# fortuna_v21_othermill.net
KiCad netlist of a schematic drawn in EAGLE
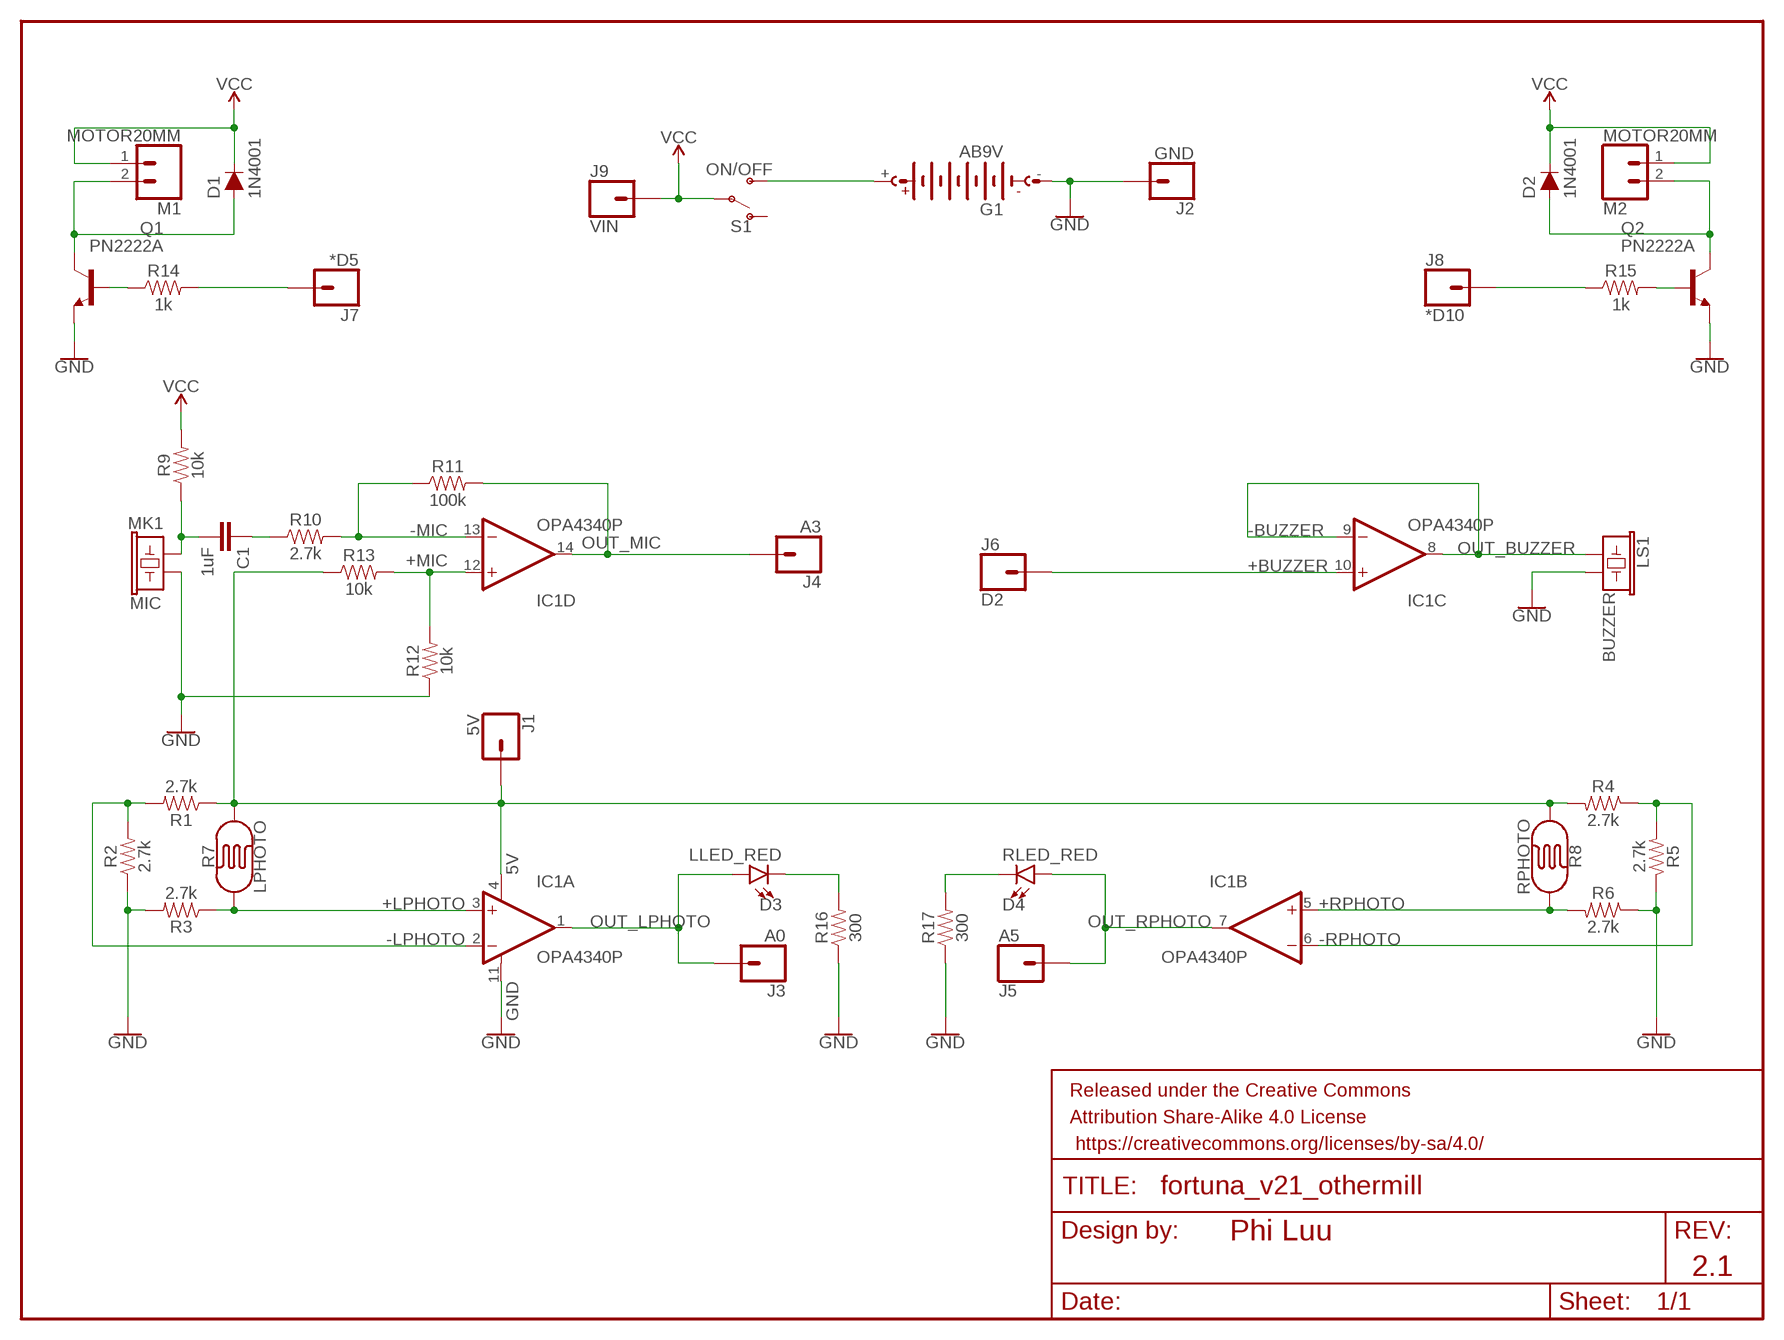
[diagram p0: schematic, sheet 1]

(export (version "E")
  (design (tool "Eeschema 10.0.6"))
  (components
    (comp (ref "C1")
      (value "1uF")
      (footprint "eagle-import:CAP-PTH-SMALL-KIT")
      (libsource (lib "eagle-import") (part "0.1UF-KIT-EZ-50V-20%"))
    )
    (comp (ref "D1")
      (value "1N4001")
      (footprint "eagle-import:DIODE-1N4001")
      (libsource (lib "eagle-import") (part "DIODE-PTH"))
    )
    (comp (ref "D2")
      (value "1N4001")
      (footprint "eagle-import:DIODE-1N4001")
      (libsource (lib "eagle-import") (part "DIODE-PTH"))
    )
    (comp (ref "D3")
      (value "LLED_RED")
      (footprint "eagle-import:LED_5MM")
      (libsource (lib "eagle-import") (part "LED5MM"))
    )
    (comp (ref "D4")
      (value "RLED_RED")
      (footprint "eagle-import:LED_5MM")
      (libsource (lib "eagle-import") (part "LED5MM"))
    )
    (comp (ref "FRAME1")
      (value "FRAME-LETTER")
      (footprint "eagle-import:CREATIVE_COMMONS")
      (libsource (lib "eagle-import") (part "FRAME-LETTER"))
    )
    (comp (ref "G1")
      (value "AB9V")
      (footprint "eagle-import:AB9V")
      (libsource (lib "eagle-import") (part "AB9V"))
    )
    (comp (ref "IC1")
      (value "OPA4340P")
      (footprint "eagle-import:DIL14")
      (libsource (lib "eagle-import") (part "OPA4340P"))
    )
    (comp (ref "J1")
      (value "5V")
      (footprint "eagle-import:1X01")
      (libsource (lib "eagle-import") (part "CONN_01"))
    )
    (comp (ref "J2")
      (value "GND")
      (footprint "eagle-import:1X01")
      (libsource (lib "eagle-import") (part "CONN_01"))
    )
    (comp (ref "J3")
      (value "A0")
      (footprint "eagle-import:1X01")
      (libsource (lib "eagle-import") (part "CONN_01"))
    )
    (comp (ref "J4")
      (value "A3")
      (footprint "eagle-import:1X01")
      (libsource (lib "eagle-import") (part "CONN_01"))
    )
    (comp (ref "J5")
      (value "A5")
      (footprint "eagle-import:1X01")
      (libsource (lib "eagle-import") (part "CONN_01"))
    )
    (comp (ref "J6")
      (value "D2")
      (footprint "eagle-import:1X01")
      (libsource (lib "eagle-import") (part "CONN_01"))
    )
    (comp (ref "J7")
      (value "*D5")
      (footprint "eagle-import:1X01")
      (libsource (lib "eagle-import") (part "CONN_01"))
    )
    (comp (ref "J8")
      (value "*D10")
      (footprint "eagle-import:1X01")
      (libsource (lib "eagle-import") (part "CONN_01"))
    )
    (comp (ref "J9")
      (value "VIN")
      (footprint "eagle-import:1X01")
      (libsource (lib "eagle-import") (part "CONN_01"))
    )
    (comp (ref "LS1")
      (value "BUZZER")
      (footprint "eagle-import:BUZZER-12MM")
      (libsource (lib "eagle-import") (part "BUZZER-PTH"))
    )
    (comp (ref "M1")
      (value "MOTOR20MM")
      (footprint "eagle-import:1X02")
      (libsource (lib "eagle-import") (part "CONN_02"))
    )
    (comp (ref "M2")
      (value "MOTOR20MM")
      (footprint "eagle-import:1X02")
      (libsource (lib "eagle-import") (part "CONN_02"))
    )
    (comp (ref "MK1")
      (value "MIC")
      (footprint "eagle-import:MICROPHONE-PTH-9.7MM")
      (libsource (lib "eagle-import") (part "MIC-PTH"))
    )
    (comp (ref "Q1")
      (value "PN2222A")
      (footprint "eagle-import:TO92-EBC-OVAL")
      (libsource (lib "eagle-import") (part "2N2222"))
    )
    (comp (ref "Q2")
      (value "PN2222A")
      (footprint "eagle-import:TO92-EBC-OVAL")
      (libsource (lib "eagle-import") (part "2N2222"))
    )
    (comp (ref "R1")
      (value "2.7k")
      (footprint "eagle-import:AXIAL-0.3")
      (libsource (lib "eagle-import") (part "1KOHM-HORIZ-1/4W-5%"))
    )
    (comp (ref "R2")
      (value "2.7k")
      (footprint "eagle-import:AXIAL-0.3")
      (libsource (lib "eagle-import") (part "1KOHM-HORIZ-1/4W-5%"))
    )
    (comp (ref "R3")
      (value "2.7k")
      (footprint "eagle-import:AXIAL-0.3")
      (libsource (lib "eagle-import") (part "1KOHM-HORIZ-1/4W-5%"))
    )
    (comp (ref "R4")
      (value "2.7k")
      (footprint "eagle-import:AXIAL-0.3")
      (libsource (lib "eagle-import") (part "1KOHM-HORIZ-1/4W-5%"))
    )
    (comp (ref "R5")
      (value "2.7k")
      (footprint "eagle-import:AXIAL-0.3")
      (libsource (lib "eagle-import") (part "1KOHM-HORIZ-1/4W-5%"))
    )
    (comp (ref "R6")
      (value "2.7k")
      (footprint "eagle-import:AXIAL-0.3")
      (libsource (lib "eagle-import") (part "1KOHM-HORIZ-1/4W-5%"))
    )
    (comp (ref "R7")
      (value "LPHOTO")
      (footprint "eagle-import:PHOTOCELL")
      (libsource (lib "eagle-import") (part "PHOTOCELLPTH"))
    )
    (comp (ref "R8")
      (value "RPHOTO")
      (footprint "eagle-import:PHOTOCELL")
      (libsource (lib "eagle-import") (part "PHOTOCELLPTH"))
    )
    (comp (ref "R9")
      (value "10k")
      (footprint "eagle-import:AXIAL-0.3")
      (libsource (lib "eagle-import") (part "1KOHM-HORIZ-1/4W-5%"))
    )
    (comp (ref "R10")
      (value "2.7k")
      (footprint "eagle-import:AXIAL-0.3")
      (libsource (lib "eagle-import") (part "1KOHM-HORIZ-1/4W-5%"))
    )
    (comp (ref "R11")
      (value "100k")
      (footprint "eagle-import:AXIAL-0.3")
      (libsource (lib "eagle-import") (part "1KOHM-HORIZ-1/4W-5%"))
    )
    (comp (ref "R12")
      (value "10k")
      (footprint "eagle-import:AXIAL-0.3")
      (libsource (lib "eagle-import") (part "1KOHM-HORIZ-1/4W-5%"))
    )
    (comp (ref "R13")
      (value "10k")
      (footprint "eagle-import:AXIAL-0.3")
      (libsource (lib "eagle-import") (part "1KOHM-HORIZ-1/4W-5%"))
    )
    (comp (ref "R14")
      (value "1k")
      (footprint "eagle-import:AXIAL-0.3")
      (libsource (lib "eagle-import") (part "1KOHM-HORIZ-1/4W-5%"))
    )
    (comp (ref "R15")
      (value "1k")
      (footprint "eagle-import:AXIAL-0.3")
      (libsource (lib "eagle-import") (part "1KOHM-HORIZ-1/4W-5%"))
    )
    (comp (ref "R16")
      (value "300")
      (footprint "eagle-import:AXIAL-0.3")
      (libsource (lib "eagle-import") (part "1KOHM-HORIZ-1/4W-5%"))
    )
    (comp (ref "R17")
      (value "300")
      (footprint "eagle-import:AXIAL-0.3")
      (libsource (lib "eagle-import") (part "1KOHM-HORIZ-1/4W-5%"))
    )
    (comp (ref "S1")
      (value "ON/OFF")
      (footprint "eagle-import:SWITCH_SPDT_PTH_11.6X4.0MM")
      (libsource (lib "eagle-import") (part "SWITCH-SPDT-PTH-11.6X4.0MM"))
    )
  )
  (nets
    (net (code "1") (name "/+LPHOTO") (class "Default")
      (node (ref "IC1") (pin "3") (pinfunction "+IN_3") (pintype "input"))
      (node (ref "R3") (pin "P$1") (pinfunction "1_P$1") (pintype "passive"))
      (node (ref "R7") (pin "1") (pinfunction "P$1_1") (pintype "bidirectional"))
    )
    (net (code "2") (name "/+MIC") (class "Default")
      (node (ref "IC1") (pin "12") (pinfunction "+IN_12") (pintype "input"))
      (node (ref "R12") (pin "P$2") (pinfunction "2_P$2") (pintype "passive"))
      (node (ref "R13") (pin "P$2") (pinfunction "2_P$2") (pintype "passive"))
    )
    (net (code "3") (name "/+RPHOTO") (class "Default")
      (node (ref "IC1") (pin "5") (pinfunction "+IN_5") (pintype "input"))
      (node (ref "R6") (pin "P$2") (pinfunction "2_P$2") (pintype "passive"))
      (node (ref "R8") (pin "1") (pinfunction "P$1_1") (pintype "bidirectional"))
    )
    (net (code "4") (name "/-LPHOTO") (class "Default")
      (node (ref "IC1") (pin "2") (pinfunction "-IN_2") (pintype "input"))
      (node (ref "R1") (pin "P$2") (pinfunction "2_P$2") (pintype "passive"))
      (node (ref "R2") (pin "P$2") (pinfunction "2_P$2") (pintype "passive"))
    )
    (net (code "5") (name "/-MIC") (class "Default")
      (node (ref "IC1") (pin "13") (pinfunction "-IN_13") (pintype "input"))
      (node (ref "R10") (pin "P$2") (pinfunction "2_P$2") (pintype "passive"))
      (node (ref "R11") (pin "P$1") (pinfunction "1_P$1") (pintype "passive"))
    )
    (net (code "6") (name "/-RPHOTO") (class "Default")
      (node (ref "IC1") (pin "6") (pinfunction "-IN_6") (pintype "input"))
      (node (ref "R4") (pin "P$1") (pinfunction "1_P$1") (pintype "passive"))
      (node (ref "R5") (pin "P$2") (pinfunction "2_P$2") (pintype "passive"))
    )
    (net (code "7") (name "/5V") (class "Default")
      (node (ref "IC1") (pin "4") (pinfunction "V+_4") (pintype "power_in"))
      (node (ref "J1") (pin "1") (pinfunction "1_1") (pintype "passive"))
      (node (ref "R1") (pin "P$1") (pinfunction "1_P$1") (pintype "passive"))
      (node (ref "R13") (pin "P$1") (pinfunction "1_P$1") (pintype "passive"))
      (node (ref "R4") (pin "P$2") (pinfunction "2_P$2") (pintype "passive"))
      (node (ref "R7") (pin "2") (pinfunction "P$2_2") (pintype "bidirectional"))
      (node (ref "R8") (pin "2") (pinfunction "P$2_2") (pintype "bidirectional"))
    )
    (net (code "8") (name "/OUT_BUZZER") (class "Default")
      (node (ref "IC1") (pin "8") (pinfunction "OUT_8") (pintype "output"))
      (node (ref "IC1") (pin "9") (pinfunction "-IN_9") (pintype "input"))
      (node (ref "LS1") (pin "+") (pinfunction "1_+") (pintype "passive"))
    )
    (net (code "9") (name "/OUT_LPHOTO") (class "Default")
      (node (ref "D3") (pin "A") (pinfunction "A_A") (pintype "passive"))
      (node (ref "IC1") (pin "1") (pinfunction "OUT_1") (pintype "output"))
      (node (ref "J3") (pin "1") (pinfunction "1_1") (pintype "passive"))
    )
    (net (code "10") (name "/OUT_MIC") (class "Default")
      (node (ref "IC1") (pin "14") (pinfunction "OUT_14") (pintype "output"))
      (node (ref "J4") (pin "1") (pinfunction "1_1") (pintype "passive"))
      (node (ref "R11") (pin "P$2") (pinfunction "2_P$2") (pintype "passive"))
    )
    (net (code "11") (name "/OUT_RPHOTO") (class "Default")
      (node (ref "D4") (pin "A") (pinfunction "A_A") (pintype "passive"))
      (node (ref "IC1") (pin "7") (pinfunction "OUT_7") (pintype "output"))
      (node (ref "J5") (pin "1") (pinfunction "1_1") (pintype "passive"))
    )
    (net (code "12") (name "GND") (class "Default")
      (node (ref "G1") (pin "-") (pinfunction "-_-") (pintype "passive"))
      (node (ref "IC1") (pin "11") (pinfunction "V-_11") (pintype "power_in"))
      (node (ref "J2") (pin "1") (pinfunction "1_1") (pintype "passive"))
      (node (ref "LS1") (pin "-") (pinfunction "2_-") (pintype "passive"))
      (node (ref "MK1") (pin "GND") (pinfunction "2_GND") (pintype "passive"))
      (node (ref "Q1") (pin "E") (pinfunction "E_E") (pintype "passive"))
      (node (ref "Q2") (pin "E") (pinfunction "E_E") (pintype "passive"))
      (node (ref "R12") (pin "P$1") (pinfunction "1_P$1") (pintype "passive"))
      (node (ref "R16") (pin "P$1") (pinfunction "1_P$1") (pintype "passive"))
      (node (ref "R17") (pin "P$1") (pinfunction "1_P$1") (pintype "passive"))
      (node (ref "R2") (pin "P$1") (pinfunction "1_P$1") (pintype "passive"))
      (node (ref "R3") (pin "P$2") (pinfunction "2_P$2") (pintype "passive"))
      (node (ref "R5") (pin "P$1") (pinfunction "1_P$1") (pintype "passive"))
      (node (ref "R6") (pin "P$1") (pinfunction "1_P$1") (pintype "passive"))
    )
    (net (code "13") (name "Net-(D1-PadA)") (class "Default")
      (node (ref "D1") (pin "A") (pinfunction "A_A") (pintype "passive"))
      (node (ref "M1") (pin "2") (pinfunction "2_2") (pintype "passive"))
      (node (ref "Q1") (pin "C") (pinfunction "C_C") (pintype "passive"))
    )
    (net (code "14") (name "Net-(D2-PadA)") (class "Default")
      (node (ref "D2") (pin "A") (pinfunction "A_A") (pintype "passive"))
      (node (ref "M2") (pin "2") (pinfunction "2_2") (pintype "passive"))
      (node (ref "Q2") (pin "C") (pinfunction "C_C") (pintype "passive"))
    )
    (net (code "15") (name "Net-(D3-C)") (class "Default")
      (node (ref "D3") (pin "K") (pinfunction "C_K") (pintype "passive"))
      (node (ref "R16") (pin "P$2") (pinfunction "2_P$2") (pintype "passive"))
    )
    (net (code "16") (name "Net-(D4-C)") (class "Default")
      (node (ref "D4") (pin "K") (pinfunction "C_K") (pintype "passive"))
      (node (ref "R17") (pin "P$2") (pinfunction "2_P$2") (pintype "passive"))
    )
    (net (code "17") (name "Net-(IC1C-+IN)") (class "Default")
      (node (ref "IC1") (pin "10") (pinfunction "+IN_10") (pintype "input"))
      (node (ref "J6") (pin "1") (pinfunction "1_1") (pintype "passive"))
    )
    (net (code "18") (name "Net-(MK1-1)") (class "Default")
      (node (ref "C1") (pin "2") (pinfunction "2_2") (pintype "passive"))
      (node (ref "MK1") (pin "OUT") (pinfunction "1_OUT") (pintype "passive"))
      (node (ref "R9") (pin "P$1") (pinfunction "1_P$1") (pintype "passive"))
    )
    (net (code "19") (name "Net-(R10-1)") (class "Default")
      (node (ref "C1") (pin "1") (pinfunction "1_1") (pintype "passive"))
      (node (ref "R10") (pin "P$1") (pinfunction "1_P$1") (pintype "passive"))
    )
    (net (code "20") (name "Net-(R14-1)") (class "Default")
      (node (ref "Q1") (pin "B") (pinfunction "B_B") (pintype "passive"))
      (node (ref "R14") (pin "P$1") (pinfunction "1_P$1") (pintype "passive"))
    )
    (net (code "21") (name "Net-(R14-2)") (class "Default")
      (node (ref "J7") (pin "1") (pinfunction "1_1") (pintype "passive"))
      (node (ref "R14") (pin "P$2") (pinfunction "2_P$2") (pintype "passive"))
    )
    (net (code "22") (name "Net-(R15-1)") (class "Default")
      (node (ref "J8") (pin "1") (pinfunction "1_1") (pintype "passive"))
      (node (ref "R15") (pin "P$1") (pinfunction "1_P$1") (pintype "passive"))
    )
    (net (code "23") (name "Net-(R15-2)") (class "Default")
      (node (ref "Q2") (pin "B") (pinfunction "B_B") (pintype "passive"))
      (node (ref "R15") (pin "P$2") (pinfunction "2_P$2") (pintype "passive"))
    )
    (net (code "24") (name "Net-(S1-S)") (class "Default")
      (node (ref "G1") (pin "+") (pinfunction "+_+") (pintype "passive"))
      (node (ref "S1") (pin "3") (pinfunction "S_3") (pintype "passive"))
    )
    (net (code "25") (name "VCC") (class "Default")
      (node (ref "D1") (pin "C") (pinfunction "C_C") (pintype "passive"))
      (node (ref "D2") (pin "C") (pinfunction "C_C") (pintype "passive"))
      (node (ref "J9") (pin "1") (pinfunction "1_1") (pintype "passive"))
      (node (ref "M1") (pin "1") (pinfunction "1_1") (pintype "passive"))
      (node (ref "M2") (pin "1") (pinfunction "1_1") (pintype "passive"))
      (node (ref "R9") (pin "P$2") (pinfunction "2_P$2") (pintype "passive"))
      (node (ref "S1") (pin "2") (pinfunction "P_2") (pintype "passive"))
    )
    (net (code "26") (name "unconnected-(S1-O-Pad1)") (class "Default")
      (node (ref "S1") (pin "1") (pinfunction "O_1") (pintype "passive"))
    )
  )
)
